# MRCS-Advanced-BiColor-Occupancy-Display_.net
KiCad netlist of a schematic drawn in EAGLE
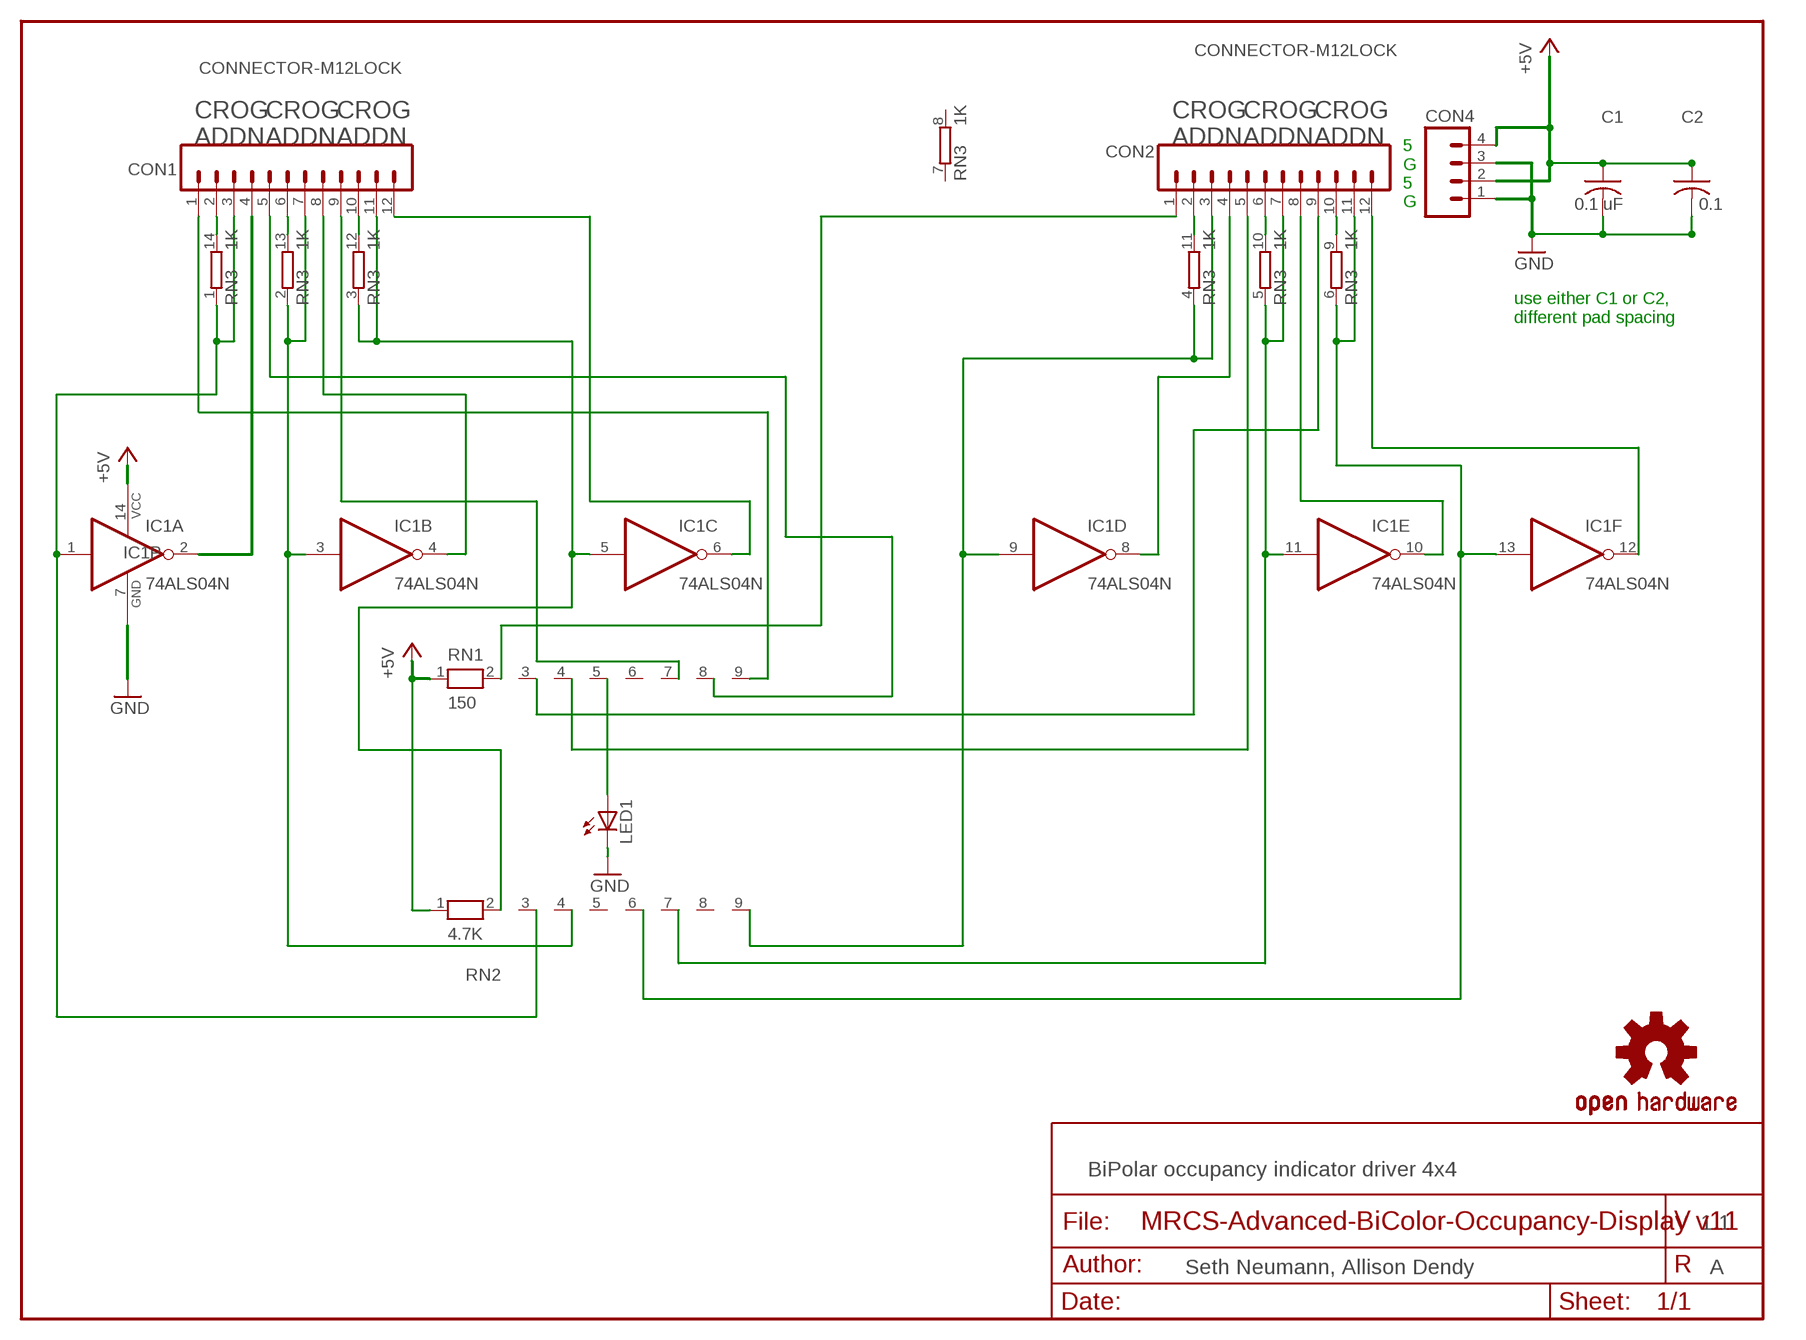
[diagram p0: schematic, sheet 1]

(export (version "E")
  (design (tool "Eeschema 10.0.6"))
  (components
    (comp (ref "C1")
      (value "0.1 uF")
      (footprint "eagle-import:C-PTH-0.100")
      (libsource (lib "eagle-import") (part "CAPPTH2"))
    )
    (comp (ref "C2")
      (value "0.1")
      (footprint "eagle-import:C050-024X044")
      (libsource (lib "eagle-import") (part "CAPPTH1"))
    )
    (comp (ref "CON1")
      (value "CONNECTOR-M12LOCK")
      (footprint "eagle-import:1X12_LOCK")
      (libsource (lib "eagle-import") (part "CONNECTOR-M12LOCK"))
    )
    (comp (ref "CON2")
      (value "CONNECTOR-M12LOCK")
      (footprint "eagle-import:1X12_LOCK")
      (libsource (lib "eagle-import") (part "CONNECTOR-M12LOCK"))
    )
    (comp (ref "CON4")
      (value "CONNECTOR-M04SCREW")
      (footprint "eagle-import:SCREWTERMINAL-3.5MM-4")
      (libsource (lib "eagle-import") (part "CONNECTOR-M04SCREW"))
    )
    (comp (ref "IC1")
      (value "74ALS04N")
      (footprint "eagle-import:DIL14")
      (libsource (lib "eagle-import") (part "7404NALS"))
    )
    (comp (ref "LED1")
      (value "LEDLED3MM")
      (footprint "eagle-import:LED3MM")
      (libsource (lib "eagle-import") (part "LEDLED3MM"))
    )
    (comp (ref "OSHW1")
      (value "DOC-OSHW-LOGO-M")
      (footprint "eagle-import:OSHW-LOGO-M")
      (libsource (lib "eagle-import") (part "DOC-OSHW-LOGO-M"))
    )
    (comp (ref "RN1")
      (value "150")
      (footprint "eagle-import:RN-9")
      (libsource (lib "eagle-import") (part "RN08"))
    )
    (comp (ref "RN2")
      (value "4.7K")
      (footprint "eagle-import:RN-9")
      (libsource (lib "eagle-import") (part "RN08"))
    )
    (comp (ref "RN3")
      (value "1K")
      (footprint "eagle-import:DIL14")
      (libsource (lib "eagle-import") (part "7R-P"))
    )
  )
  (nets
    (net (code "1") (name "+5V") (class "Default")
      (node (ref "C1") (pin "1") (pinfunction "1_1") (pintype "passive"))
      (node (ref "C2") (pin "1") (pinfunction "1_1") (pintype "passive"))
      (node (ref "CON4") (pin "2") (pinfunction "2_2") (pintype "passive"))
      (node (ref "CON4") (pin "4") (pinfunction "4_4") (pintype "passive"))
      (node (ref "IC1") (pin "14") (pinfunction "VCC_14") (pintype "power_in"))
      (node (ref "RN1") (pin "1") (pinfunction "1_1") (pintype "passive"))
      (node (ref "RN2") (pin "1") (pinfunction "1_1") (pintype "passive"))
    )
    (net (code "2") (name "GND") (class "Default")
      (node (ref "C1") (pin "2") (pinfunction "2_2") (pintype "passive"))
      (node (ref "C2") (pin "2") (pinfunction "2_2") (pintype "passive"))
      (node (ref "CON4") (pin "1") (pinfunction "1_1") (pintype "passive"))
      (node (ref "CON4") (pin "3") (pinfunction "3_3") (pintype "passive"))
      (node (ref "IC1") (pin "7") (pinfunction "GND_7") (pintype "power_in"))
      (node (ref "LED1") (pin "K") (pinfunction "C_K") (pintype "passive"))
    )
    (net (code "3") (name "Net-(CON1-Pad1)") (class "Default")
      (node (ref "CON1") (pin "1") (pinfunction "1_1") (pintype "passive"))
      (node (ref "RN1") (pin "9") (pinfunction "9_9") (pintype "passive"))
    )
    (net (code "4") (name "Net-(CON1-Pad5)") (class "Default")
      (node (ref "CON1") (pin "5") (pinfunction "5_5") (pintype "passive"))
      (node (ref "RN1") (pin "8") (pinfunction "8_8") (pintype "passive"))
    )
    (net (code "5") (name "Net-(CON1-Pad9)") (class "Default")
      (node (ref "CON1") (pin "9") (pinfunction "9_9") (pintype "passive"))
      (node (ref "RN1") (pin "7") (pinfunction "7_7") (pintype "passive"))
    )
    (net (code "6") (name "Net-(CON2-Pad1)") (class "Default")
      (node (ref "CON2") (pin "1") (pinfunction "1_1") (pintype "passive"))
      (node (ref "RN1") (pin "2") (pinfunction "2_2") (pintype "passive"))
    )
    (net (code "7") (name "Net-(CON2-Pad5)") (class "Default")
      (node (ref "CON2") (pin "5") (pinfunction "5_5") (pintype "passive"))
      (node (ref "RN1") (pin "4") (pinfunction "4_4") (pintype "passive"))
    )
    (net (code "8") (name "Net-(CON2-Pad9)") (class "Default")
      (node (ref "CON2") (pin "9") (pinfunction "9_9") (pintype "passive"))
      (node (ref "RN1") (pin "3") (pinfunction "3_3") (pintype "passive"))
    )
    (net (code "9") (name "Net-(IC1A-I)") (class "Default")
      (node (ref "CON1") (pin "3") (pinfunction "3_3") (pintype "passive"))
      (node (ref "IC1") (pin "1") (pinfunction "I_1") (pintype "input"))
      (node (ref "RN2") (pin "3") (pinfunction "3_3") (pintype "passive"))
      (node (ref "RN3") (pin "1") (pinfunction "1_1") (pintype "passive"))
    )
    (net (code "10") (name "Net-(IC1A-O)") (class "Default")
      (node (ref "CON1") (pin "4") (pinfunction "4_4") (pintype "passive"))
      (node (ref "IC1") (pin "2") (pinfunction "O_2") (pintype "output"))
    )
    (net (code "11") (name "Net-(IC1B-I)") (class "Default")
      (node (ref "CON1") (pin "7") (pinfunction "7_7") (pintype "passive"))
      (node (ref "IC1") (pin "3") (pinfunction "I_3") (pintype "input"))
      (node (ref "RN2") (pin "4") (pinfunction "4_4") (pintype "passive"))
      (node (ref "RN3") (pin "2") (pinfunction "1_2") (pintype "passive"))
    )
    (net (code "12") (name "Net-(IC1B-O)") (class "Default")
      (node (ref "CON1") (pin "8") (pinfunction "8_8") (pintype "passive"))
      (node (ref "IC1") (pin "4") (pinfunction "O_4") (pintype "output"))
    )
    (net (code "13") (name "Net-(IC1C-I)") (class "Default")
      (node (ref "CON1") (pin "11") (pinfunction "11_11") (pintype "passive"))
      (node (ref "IC1") (pin "5") (pinfunction "I_5") (pintype "input"))
      (node (ref "RN2") (pin "2") (pinfunction "2_2") (pintype "passive"))
      (node (ref "RN3") (pin "3") (pinfunction "1_3") (pintype "passive"))
    )
    (net (code "14") (name "Net-(IC1C-O)") (class "Default")
      (node (ref "CON1") (pin "12") (pinfunction "12_12") (pintype "passive"))
      (node (ref "IC1") (pin "6") (pinfunction "O_6") (pintype "output"))
    )
    (net (code "15") (name "Net-(IC1D-I)") (class "Default")
      (node (ref "CON2") (pin "3") (pinfunction "3_3") (pintype "passive"))
      (node (ref "IC1") (pin "9") (pinfunction "I_9") (pintype "input"))
      (node (ref "RN2") (pin "9") (pinfunction "9_9") (pintype "passive"))
      (node (ref "RN3") (pin "4") (pinfunction "1_4") (pintype "passive"))
    )
    (net (code "16") (name "Net-(IC1D-O)") (class "Default")
      (node (ref "CON2") (pin "4") (pinfunction "4_4") (pintype "passive"))
      (node (ref "IC1") (pin "8") (pinfunction "O_8") (pintype "output"))
    )
    (net (code "17") (name "Net-(IC1E-I)") (class "Default")
      (node (ref "CON2") (pin "7") (pinfunction "7_7") (pintype "passive"))
      (node (ref "IC1") (pin "11") (pinfunction "I_11") (pintype "input"))
      (node (ref "RN2") (pin "7") (pinfunction "7_7") (pintype "passive"))
      (node (ref "RN3") (pin "5") (pinfunction "1_5") (pintype "passive"))
    )
    (net (code "18") (name "Net-(IC1E-O)") (class "Default")
      (node (ref "CON2") (pin "8") (pinfunction "8_8") (pintype "passive"))
      (node (ref "IC1") (pin "10") (pinfunction "O_10") (pintype "output"))
    )
    (net (code "19") (name "Net-(IC1F-I)") (class "Default")
      (node (ref "CON2") (pin "11") (pinfunction "11_11") (pintype "passive"))
      (node (ref "IC1") (pin "13") (pinfunction "I_13") (pintype "input"))
      (node (ref "RN2") (pin "6") (pinfunction "6_6") (pintype "passive"))
      (node (ref "RN3") (pin "6") (pinfunction "1_6") (pintype "passive"))
    )
    (net (code "20") (name "Net-(IC1F-O)") (class "Default")
      (node (ref "CON2") (pin "12") (pinfunction "12_12") (pintype "passive"))
      (node (ref "IC1") (pin "12") (pinfunction "O_12") (pintype "output"))
    )
    (net (code "21") (name "Net-(LED1-PadA)") (class "Default")
      (node (ref "LED1") (pin "A") (pinfunction "A_A") (pintype "passive"))
      (node (ref "RN1") (pin "5") (pinfunction "5_5") (pintype "passive"))
    )
    (net (code "22") (name "Net-(RN3A-2)") (class "Default")
      (node (ref "CON1") (pin "2") (pinfunction "2_2") (pintype "passive"))
      (node (ref "RN3") (pin "14") (pinfunction "2_14") (pintype "passive"))
    )
    (net (code "23") (name "Net-(RN3B-2)") (class "Default")
      (node (ref "CON1") (pin "6") (pinfunction "6_6") (pintype "passive"))
      (node (ref "RN3") (pin "13") (pinfunction "2_13") (pintype "passive"))
    )
    (net (code "24") (name "Net-(RN3C-2)") (class "Default")
      (node (ref "CON1") (pin "10") (pinfunction "10_10") (pintype "passive"))
      (node (ref "RN3") (pin "12") (pinfunction "2_12") (pintype "passive"))
    )
    (net (code "25") (name "Net-(RN3D-2)") (class "Default")
      (node (ref "CON2") (pin "2") (pinfunction "2_2") (pintype "passive"))
      (node (ref "RN3") (pin "11") (pinfunction "2_11") (pintype "passive"))
    )
    (net (code "26") (name "Net-(RN3E-2)") (class "Default")
      (node (ref "CON2") (pin "6") (pinfunction "6_6") (pintype "passive"))
      (node (ref "RN3") (pin "10") (pinfunction "2_10") (pintype "passive"))
    )
    (net (code "27") (name "Net-(RN3F-2)") (class "Default")
      (node (ref "CON2") (pin "10") (pinfunction "10_10") (pintype "passive"))
      (node (ref "RN3") (pin "9") (pinfunction "2_9") (pintype "passive"))
    )
    (net (code "28") (name "unconnected-(RN1-Pad6)") (class "Default")
      (node (ref "RN1") (pin "6") (pinfunction "6_6") (pintype "passive"))
    )
    (net (code "29") (name "unconnected-(RN2-Pad5)") (class "Default")
      (node (ref "RN2") (pin "5") (pinfunction "5_5") (pintype "passive"))
    )
    (net (code "30") (name "unconnected-(RN2-Pad8)") (class "Default")
      (node (ref "RN2") (pin "8") (pinfunction "8_8") (pintype "passive"))
    )
    (net (code "31") (name "unconnected-(RN3G-1-Pad7)") (class "Default")
      (node (ref "RN3") (pin "7") (pinfunction "1_7") (pintype "passive"))
    )
    (net (code "32") (name "unconnected-(RN3G-2-Pad8)") (class "Default")
      (node (ref "RN3") (pin "8") (pinfunction "2_8") (pintype "passive"))
    )
  )
)
